# led_slave_2x2.net
KiCad netlist of a schematic drawn in EAGLE
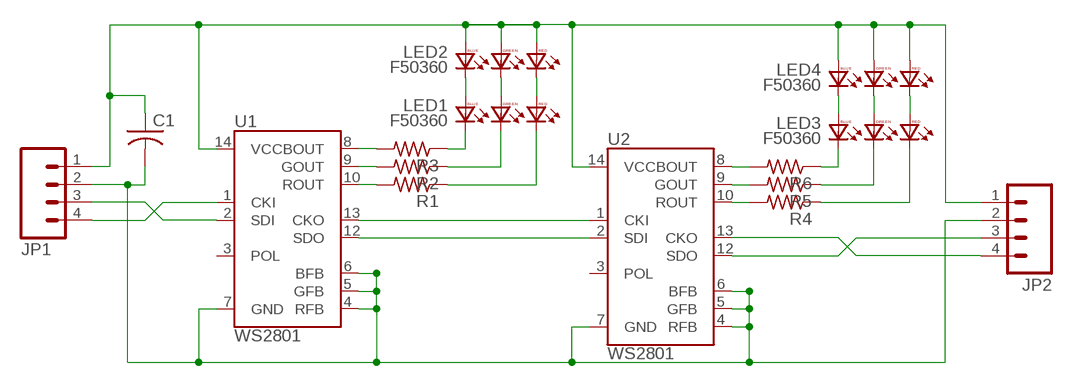
[diagram p0: schematic, sheet 1]
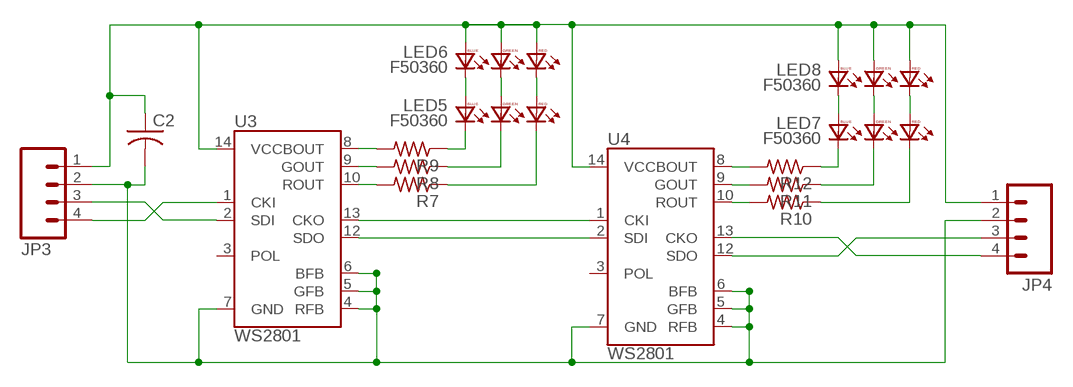
[diagram p1: schematic, sheet 2]

(export (version "E")
  (design (tool "Eeschema 10.0.6"))
  (components
    (comp (ref "C1")
      (value "C-USC1206")
      (footprint "eagle-import:C1206")
      (libsource (lib "eagle-import") (part "C-USC1206"))
    )
    (comp (ref "JP1")
      (value "M04LONGPADS")
      (footprint "eagle-import:1X04_LONGPADS")
      (libsource (lib "eagle-import") (part "M04LONGPADS"))
    )
    (comp (ref "JP2")
      (value "M04LONGPADS")
      (footprint "eagle-import:1X04_LONGPADS")
      (libsource (lib "eagle-import") (part "M04LONGPADS"))
    )
    (comp (ref "LED1")
      (value "F50360")
      (footprint "eagle-import:F50360")
      (libsource (lib "eagle-import") (part "F50360"))
    )
    (comp (ref "LED2")
      (value "F50360")
      (footprint "eagle-import:F50360")
      (libsource (lib "eagle-import") (part "F50360"))
    )
    (comp (ref "LED3")
      (value "F50360")
      (footprint "eagle-import:F50360")
      (libsource (lib "eagle-import") (part "F50360"))
    )
    (comp (ref "LED4")
      (value "F50360")
      (footprint "eagle-import:F50360")
      (libsource (lib "eagle-import") (part "F50360"))
    )
    (comp (ref "R1")
      (value "R-US_R1206")
      (footprint "eagle-import:R1206")
      (libsource (lib "eagle-import") (part "R-US_R1206"))
    )
    (comp (ref "R2")
      (value "R-US_R1206")
      (footprint "eagle-import:R1206")
      (libsource (lib "eagle-import") (part "R-US_R1206"))
    )
    (comp (ref "R3")
      (value "R-US_R1206")
      (footprint "eagle-import:R1206")
      (libsource (lib "eagle-import") (part "R-US_R1206"))
    )
    (comp (ref "R4")
      (value "R-US_R1206")
      (footprint "eagle-import:R1206")
      (libsource (lib "eagle-import") (part "R-US_R1206"))
    )
    (comp (ref "R5")
      (value "R-US_R1206")
      (footprint "eagle-import:R1206")
      (libsource (lib "eagle-import") (part "R-US_R1206"))
    )
    (comp (ref "R6")
      (value "R-US_R1206")
      (footprint "eagle-import:R1206")
      (libsource (lib "eagle-import") (part "R-US_R1206"))
    )
    (comp (ref "U1")
      (value "WS2801")
      (footprint "eagle-import:SOP-14")
      (libsource (lib "eagle-import") (part "WS2801"))
    )
    (comp (ref "U2")
      (value "WS2801")
      (footprint "eagle-import:SOP-14")
      (libsource (lib "eagle-import") (part "WS2801"))
    )
    (comp (ref "C2")
      (value "C-USC1206")
      (footprint "eagle-import:C1206")
      (libsource (lib "eagle-import") (part "C-USC1206"))
    )
    (comp (ref "JP3")
      (value "M04LONGPADS")
      (footprint "eagle-import:1X04_LONGPADS")
      (libsource (lib "eagle-import") (part "M04LONGPADS"))
    )
    (comp (ref "JP4")
      (value "M04LONGPADS")
      (footprint "eagle-import:1X04_LONGPADS")
      (libsource (lib "eagle-import") (part "M04LONGPADS"))
    )
    (comp (ref "LED5")
      (value "F50360")
      (footprint "eagle-import:F50360")
      (libsource (lib "eagle-import") (part "F50360"))
    )
    (comp (ref "LED6")
      (value "F50360")
      (footprint "eagle-import:F50360")
      (libsource (lib "eagle-import") (part "F50360"))
    )
    (comp (ref "LED7")
      (value "F50360")
      (footprint "eagle-import:F50360")
      (libsource (lib "eagle-import") (part "F50360"))
    )
    (comp (ref "LED8")
      (value "F50360")
      (footprint "eagle-import:F50360")
      (libsource (lib "eagle-import") (part "F50360"))
    )
    (comp (ref "R7")
      (value "R-US_R1206")
      (footprint "eagle-import:R1206")
      (libsource (lib "eagle-import") (part "R-US_R1206"))
    )
    (comp (ref "R8")
      (value "R-US_R1206")
      (footprint "eagle-import:R1206")
      (libsource (lib "eagle-import") (part "R-US_R1206"))
    )
    (comp (ref "R9")
      (value "R-US_R1206")
      (footprint "eagle-import:R1206")
      (libsource (lib "eagle-import") (part "R-US_R1206"))
    )
    (comp (ref "R10")
      (value "R-US_R1206")
      (footprint "eagle-import:R1206")
      (libsource (lib "eagle-import") (part "R-US_R1206"))
    )
    (comp (ref "R11")
      (value "R-US_R1206")
      (footprint "eagle-import:R1206")
      (libsource (lib "eagle-import") (part "R-US_R1206"))
    )
    (comp (ref "R12")
      (value "R-US_R1206")
      (footprint "eagle-import:R1206")
      (libsource (lib "eagle-import") (part "R-US_R1206"))
    )
    (comp (ref "U3")
      (value "WS2801")
      (footprint "eagle-import:SOP-14")
      (libsource (lib "eagle-import") (part "WS2801"))
    )
    (comp (ref "U4")
      (value "WS2801")
      (footprint "eagle-import:SOP-14")
      (libsource (lib "eagle-import") (part "WS2801"))
    )
  )
  (nets
    (net (code "1") (name "Net-(LED1-PadBA)") (class "Default")
      (node (ref "LED1") (pin "BA") (pinfunction "BA_BA") (pintype "passive"))
      (node (ref "LED2") (pin "BC") (pinfunction "BC_BC") (pintype "passive"))
    )
    (net (code "2") (name "Net-(LED1-PadBC)") (class "Default")
      (node (ref "LED1") (pin "BC") (pinfunction "BC_BC") (pintype "passive"))
      (node (ref "R3") (pin "1") (pinfunction "1_1") (pintype "passive"))
    )
    (net (code "3") (name "Net-(LED1-PadGA)") (class "Default")
      (node (ref "LED1") (pin "GA") (pinfunction "GA_GA") (pintype "passive"))
      (node (ref "LED2") (pin "GC") (pinfunction "GC_GC") (pintype "passive"))
    )
    (net (code "4") (name "Net-(LED1-PadGC)") (class "Default")
      (node (ref "LED1") (pin "GC") (pinfunction "GC_GC") (pintype "passive"))
      (node (ref "R2") (pin "1") (pinfunction "1_1") (pintype "passive"))
    )
    (net (code "5") (name "Net-(LED1-PadRA)") (class "Default")
      (node (ref "LED1") (pin "RA") (pinfunction "RA_RA") (pintype "passive"))
      (node (ref "LED2") (pin "RC") (pinfunction "RC_RC") (pintype "passive"))
    )
    (net (code "6") (name "Net-(LED1-PadRC)") (class "Default")
      (node (ref "LED1") (pin "RC") (pinfunction "RC_RC") (pintype "passive"))
      (node (ref "R1") (pin "1") (pinfunction "1_1") (pintype "passive"))
    )
    (net (code "7") (name "Net-(LED3-PadBA)") (class "Default")
      (node (ref "LED3") (pin "BA") (pinfunction "BA_BA") (pintype "passive"))
      (node (ref "LED4") (pin "BC") (pinfunction "BC_BC") (pintype "passive"))
    )
    (net (code "8") (name "Net-(LED3-PadBC)") (class "Default")
      (node (ref "LED3") (pin "BC") (pinfunction "BC_BC") (pintype "passive"))
      (node (ref "R6") (pin "1") (pinfunction "1_1") (pintype "passive"))
    )
    (net (code "9") (name "Net-(LED3-PadGA)") (class "Default")
      (node (ref "LED3") (pin "GA") (pinfunction "GA_GA") (pintype "passive"))
      (node (ref "LED4") (pin "GC") (pinfunction "GC_GC") (pintype "passive"))
    )
    (net (code "10") (name "Net-(LED3-PadGC)") (class "Default")
      (node (ref "LED3") (pin "GC") (pinfunction "GC_GC") (pintype "passive"))
      (node (ref "R5") (pin "1") (pinfunction "1_1") (pintype "passive"))
    )
    (net (code "11") (name "Net-(LED3-PadRA)") (class "Default")
      (node (ref "LED3") (pin "RA") (pinfunction "RA_RA") (pintype "passive"))
      (node (ref "LED4") (pin "RC") (pinfunction "RC_RC") (pintype "passive"))
    )
    (net (code "12") (name "Net-(LED3-PadRC)") (class "Default")
      (node (ref "LED3") (pin "RC") (pinfunction "RC_RC") (pintype "passive"))
      (node (ref "R4") (pin "1") (pinfunction "1_1") (pintype "passive"))
    )
    (net (code "13") (name "Net-(LED5-PadBA)") (class "Default")
      (node (ref "LED5") (pin "BA") (pinfunction "BA_BA") (pintype "passive"))
      (node (ref "LED6") (pin "BC") (pinfunction "BC_BC") (pintype "passive"))
    )
    (net (code "14") (name "Net-(LED5-PadBC)") (class "Default")
      (node (ref "LED5") (pin "BC") (pinfunction "BC_BC") (pintype "passive"))
      (node (ref "R9") (pin "1") (pinfunction "1_1") (pintype "passive"))
    )
    (net (code "15") (name "Net-(LED5-PadGA)") (class "Default")
      (node (ref "LED5") (pin "GA") (pinfunction "GA_GA") (pintype "passive"))
      (node (ref "LED6") (pin "GC") (pinfunction "GC_GC") (pintype "passive"))
    )
    (net (code "16") (name "Net-(LED5-PadGC)") (class "Default")
      (node (ref "LED5") (pin "GC") (pinfunction "GC_GC") (pintype "passive"))
      (node (ref "R8") (pin "1") (pinfunction "1_1") (pintype "passive"))
    )
    (net (code "17") (name "Net-(LED5-PadRA)") (class "Default")
      (node (ref "LED5") (pin "RA") (pinfunction "RA_RA") (pintype "passive"))
      (node (ref "LED6") (pin "RC") (pinfunction "RC_RC") (pintype "passive"))
    )
    (net (code "18") (name "Net-(LED5-PadRC)") (class "Default")
      (node (ref "LED5") (pin "RC") (pinfunction "RC_RC") (pintype "passive"))
      (node (ref "R7") (pin "1") (pinfunction "1_1") (pintype "passive"))
    )
    (net (code "19") (name "Net-(LED7-PadBA)") (class "Default")
      (node (ref "LED7") (pin "BA") (pinfunction "BA_BA") (pintype "passive"))
      (node (ref "LED8") (pin "BC") (pinfunction "BC_BC") (pintype "passive"))
    )
    (net (code "20") (name "Net-(LED7-PadBC)") (class "Default")
      (node (ref "LED7") (pin "BC") (pinfunction "BC_BC") (pintype "passive"))
      (node (ref "R12") (pin "1") (pinfunction "1_1") (pintype "passive"))
    )
    (net (code "21") (name "Net-(LED7-PadGA)") (class "Default")
      (node (ref "LED7") (pin "GA") (pinfunction "GA_GA") (pintype "passive"))
      (node (ref "LED8") (pin "GC") (pinfunction "GC_GC") (pintype "passive"))
    )
    (net (code "22") (name "Net-(LED7-PadGC)") (class "Default")
      (node (ref "LED7") (pin "GC") (pinfunction "GC_GC") (pintype "passive"))
      (node (ref "R11") (pin "1") (pinfunction "1_1") (pintype "passive"))
    )
    (net (code "23") (name "Net-(LED7-PadRA)") (class "Default")
      (node (ref "LED7") (pin "RA") (pinfunction "RA_RA") (pintype "passive"))
      (node (ref "LED8") (pin "RC") (pinfunction "RC_RC") (pintype "passive"))
    )
    (net (code "24") (name "Net-(LED7-PadRC)") (class "Default")
      (node (ref "LED7") (pin "RC") (pinfunction "RC_RC") (pintype "passive"))
      (node (ref "R10") (pin "1") (pinfunction "1_1") (pintype "passive"))
    )
    (net (code "25") (name "Net-(U1-BFB)") (class "Default")
      (node (ref "C1") (pin "2") (pinfunction "2_2") (pintype "passive"))
      (node (ref "JP1") (pin "2") (pinfunction "2_2") (pintype "passive"))
      (node (ref "JP2") (pin "2") (pinfunction "2_2") (pintype "passive"))
      (node (ref "U1") (pin "4") (pinfunction "RFB_4") (pintype "bidirectional"))
      (node (ref "U1") (pin "5") (pinfunction "GFB_5") (pintype "bidirectional"))
      (node (ref "U1") (pin "6") (pinfunction "BFB_6") (pintype "bidirectional"))
      (node (ref "U1") (pin "7") (pinfunction "GND_7") (pintype "bidirectional"))
      (node (ref "U2") (pin "4") (pinfunction "RFB_4") (pintype "bidirectional"))
      (node (ref "U2") (pin "5") (pinfunction "GFB_5") (pintype "bidirectional"))
      (node (ref "U2") (pin "6") (pinfunction "BFB_6") (pintype "bidirectional"))
      (node (ref "U2") (pin "7") (pinfunction "GND_7") (pintype "bidirectional"))
    )
    (net (code "26") (name "Net-(U1-BOUT)") (class "Default")
      (node (ref "R3") (pin "2") (pinfunction "2_2") (pintype "passive"))
      (node (ref "U1") (pin "8") (pinfunction "BOUT_8") (pintype "bidirectional"))
    )
    (net (code "27") (name "Net-(U1-CKI)") (class "Default")
      (node (ref "JP1") (pin "4") (pinfunction "4_4") (pintype "passive"))
      (node (ref "U1") (pin "1") (pinfunction "CKI_1") (pintype "bidirectional"))
    )
    (net (code "28") (name "Net-(U1-CKO)") (class "Default")
      (node (ref "U1") (pin "13") (pinfunction "CKO_13") (pintype "bidirectional"))
      (node (ref "U2") (pin "1") (pinfunction "CKI_1") (pintype "bidirectional"))
    )
    (net (code "29") (name "Net-(U1-GOUT)") (class "Default")
      (node (ref "R2") (pin "2") (pinfunction "2_2") (pintype "passive"))
      (node (ref "U1") (pin "9") (pinfunction "GOUT_9") (pintype "bidirectional"))
    )
    (net (code "30") (name "Net-(U1-ROUT)") (class "Default")
      (node (ref "R1") (pin "2") (pinfunction "2_2") (pintype "passive"))
      (node (ref "U1") (pin "10") (pinfunction "ROUT_10") (pintype "bidirectional"))
    )
    (net (code "31") (name "Net-(U1-SDI)") (class "Default")
      (node (ref "JP1") (pin "3") (pinfunction "3_3") (pintype "passive"))
      (node (ref "U1") (pin "2") (pinfunction "SDI_2") (pintype "bidirectional"))
    )
    (net (code "32") (name "Net-(U1-SDO)") (class "Default")
      (node (ref "U1") (pin "12") (pinfunction "SDO_12") (pintype "bidirectional"))
      (node (ref "U2") (pin "2") (pinfunction "SDI_2") (pintype "bidirectional"))
    )
    (net (code "33") (name "Net-(U1-VCC)") (class "Default")
      (node (ref "C1") (pin "1") (pinfunction "1_1") (pintype "passive"))
      (node (ref "JP1") (pin "1") (pinfunction "1_1") (pintype "passive"))
      (node (ref "JP2") (pin "1") (pinfunction "1_1") (pintype "passive"))
      (node (ref "LED2") (pin "BA") (pinfunction "BA_BA") (pintype "passive"))
      (node (ref "LED2") (pin "GA") (pinfunction "GA_GA") (pintype "passive"))
      (node (ref "LED2") (pin "RA") (pinfunction "RA_RA") (pintype "passive"))
      (node (ref "LED4") (pin "BA") (pinfunction "BA_BA") (pintype "passive"))
      (node (ref "LED4") (pin "GA") (pinfunction "GA_GA") (pintype "passive"))
      (node (ref "LED4") (pin "RA") (pinfunction "RA_RA") (pintype "passive"))
      (node (ref "U1") (pin "14") (pinfunction "VCC_14") (pintype "bidirectional"))
      (node (ref "U2") (pin "14") (pinfunction "VCC_14") (pintype "bidirectional"))
    )
    (net (code "34") (name "Net-(U2-BOUT)") (class "Default")
      (node (ref "R6") (pin "2") (pinfunction "2_2") (pintype "passive"))
      (node (ref "U2") (pin "8") (pinfunction "BOUT_8") (pintype "bidirectional"))
    )
    (net (code "35") (name "Net-(U2-CKO)") (class "Default")
      (node (ref "JP2") (pin "4") (pinfunction "4_4") (pintype "passive"))
      (node (ref "U2") (pin "13") (pinfunction "CKO_13") (pintype "bidirectional"))
    )
    (net (code "36") (name "Net-(U2-GOUT)") (class "Default")
      (node (ref "R5") (pin "2") (pinfunction "2_2") (pintype "passive"))
      (node (ref "U2") (pin "9") (pinfunction "GOUT_9") (pintype "bidirectional"))
    )
    (net (code "37") (name "Net-(U2-ROUT)") (class "Default")
      (node (ref "R4") (pin "2") (pinfunction "2_2") (pintype "passive"))
      (node (ref "U2") (pin "10") (pinfunction "ROUT_10") (pintype "bidirectional"))
    )
    (net (code "38") (name "Net-(U2-SDO)") (class "Default")
      (node (ref "JP2") (pin "3") (pinfunction "3_3") (pintype "passive"))
      (node (ref "U2") (pin "12") (pinfunction "SDO_12") (pintype "bidirectional"))
    )
    (net (code "39") (name "Net-(U3-BFB)") (class "Default")
      (node (ref "C2") (pin "2") (pinfunction "2_2") (pintype "passive"))
      (node (ref "JP3") (pin "2") (pinfunction "2_2") (pintype "passive"))
      (node (ref "JP4") (pin "2") (pinfunction "2_2") (pintype "passive"))
      (node (ref "U3") (pin "4") (pinfunction "RFB_4") (pintype "bidirectional"))
      (node (ref "U3") (pin "5") (pinfunction "GFB_5") (pintype "bidirectional"))
      (node (ref "U3") (pin "6") (pinfunction "BFB_6") (pintype "bidirectional"))
      (node (ref "U3") (pin "7") (pinfunction "GND_7") (pintype "bidirectional"))
      (node (ref "U4") (pin "4") (pinfunction "RFB_4") (pintype "bidirectional"))
      (node (ref "U4") (pin "5") (pinfunction "GFB_5") (pintype "bidirectional"))
      (node (ref "U4") (pin "6") (pinfunction "BFB_6") (pintype "bidirectional"))
      (node (ref "U4") (pin "7") (pinfunction "GND_7") (pintype "bidirectional"))
    )
    (net (code "40") (name "Net-(U3-BOUT)") (class "Default")
      (node (ref "R9") (pin "2") (pinfunction "2_2") (pintype "passive"))
      (node (ref "U3") (pin "8") (pinfunction "BOUT_8") (pintype "bidirectional"))
    )
    (net (code "41") (name "Net-(U3-CKI)") (class "Default")
      (node (ref "JP3") (pin "4") (pinfunction "4_4") (pintype "passive"))
      (node (ref "U3") (pin "1") (pinfunction "CKI_1") (pintype "bidirectional"))
    )
    (net (code "42") (name "Net-(U3-CKO)") (class "Default")
      (node (ref "U3") (pin "13") (pinfunction "CKO_13") (pintype "bidirectional"))
      (node (ref "U4") (pin "1") (pinfunction "CKI_1") (pintype "bidirectional"))
    )
    (net (code "43") (name "Net-(U3-GOUT)") (class "Default")
      (node (ref "R8") (pin "2") (pinfunction "2_2") (pintype "passive"))
      (node (ref "U3") (pin "9") (pinfunction "GOUT_9") (pintype "bidirectional"))
    )
    (net (code "44") (name "Net-(U3-ROUT)") (class "Default")
      (node (ref "R7") (pin "2") (pinfunction "2_2") (pintype "passive"))
      (node (ref "U3") (pin "10") (pinfunction "ROUT_10") (pintype "bidirectional"))
    )
    (net (code "45") (name "Net-(U3-SDI)") (class "Default")
      (node (ref "JP3") (pin "3") (pinfunction "3_3") (pintype "passive"))
      (node (ref "U3") (pin "2") (pinfunction "SDI_2") (pintype "bidirectional"))
    )
    (net (code "46") (name "Net-(U3-SDO)") (class "Default")
      (node (ref "U3") (pin "12") (pinfunction "SDO_12") (pintype "bidirectional"))
      (node (ref "U4") (pin "2") (pinfunction "SDI_2") (pintype "bidirectional"))
    )
    (net (code "47") (name "Net-(U3-VCC)") (class "Default")
      (node (ref "C2") (pin "1") (pinfunction "1_1") (pintype "passive"))
      (node (ref "JP3") (pin "1") (pinfunction "1_1") (pintype "passive"))
      (node (ref "JP4") (pin "1") (pinfunction "1_1") (pintype "passive"))
      (node (ref "LED6") (pin "BA") (pinfunction "BA_BA") (pintype "passive"))
      (node (ref "LED6") (pin "GA") (pinfunction "GA_GA") (pintype "passive"))
      (node (ref "LED6") (pin "RA") (pinfunction "RA_RA") (pintype "passive"))
      (node (ref "LED8") (pin "BA") (pinfunction "BA_BA") (pintype "passive"))
      (node (ref "LED8") (pin "GA") (pinfunction "GA_GA") (pintype "passive"))
      (node (ref "LED8") (pin "RA") (pinfunction "RA_RA") (pintype "passive"))
      (node (ref "U3") (pin "14") (pinfunction "VCC_14") (pintype "bidirectional"))
      (node (ref "U4") (pin "14") (pinfunction "VCC_14") (pintype "bidirectional"))
    )
    (net (code "48") (name "Net-(U4-BOUT)") (class "Default")
      (node (ref "R12") (pin "2") (pinfunction "2_2") (pintype "passive"))
      (node (ref "U4") (pin "8") (pinfunction "BOUT_8") (pintype "bidirectional"))
    )
    (net (code "49") (name "Net-(U4-CKO)") (class "Default")
      (node (ref "JP4") (pin "4") (pinfunction "4_4") (pintype "passive"))
      (node (ref "U4") (pin "13") (pinfunction "CKO_13") (pintype "bidirectional"))
    )
    (net (code "50") (name "Net-(U4-GOUT)") (class "Default")
      (node (ref "R11") (pin "2") (pinfunction "2_2") (pintype "passive"))
      (node (ref "U4") (pin "9") (pinfunction "GOUT_9") (pintype "bidirectional"))
    )
    (net (code "51") (name "Net-(U4-ROUT)") (class "Default")
      (node (ref "R10") (pin "2") (pinfunction "2_2") (pintype "passive"))
      (node (ref "U4") (pin "10") (pinfunction "ROUT_10") (pintype "bidirectional"))
    )
    (net (code "52") (name "Net-(U4-SDO)") (class "Default")
      (node (ref "JP4") (pin "3") (pinfunction "3_3") (pintype "passive"))
      (node (ref "U4") (pin "12") (pinfunction "SDO_12") (pintype "bidirectional"))
    )
    (net (code "53") (name "unconnected-(U1-POL-Pad3)") (class "Default")
      (node (ref "U1") (pin "3") (pinfunction "POL_3") (pintype "bidirectional"))
    )
    (net (code "54") (name "unconnected-(U2-POL-Pad3)") (class "Default")
      (node (ref "U2") (pin "3") (pinfunction "POL_3") (pintype "bidirectional"))
    )
    (net (code "55") (name "unconnected-(U3-POL-Pad3)") (class "Default")
      (node (ref "U3") (pin "3") (pinfunction "POL_3") (pintype "bidirectional"))
    )
    (net (code "56") (name "unconnected-(U4-POL-Pad3)") (class "Default")
      (node (ref "U4") (pin "3") (pinfunction "POL_3") (pintype "bidirectional"))
    )
  )
)
